# uno.net
KiCad netlist of a schematic drawn in EAGLE
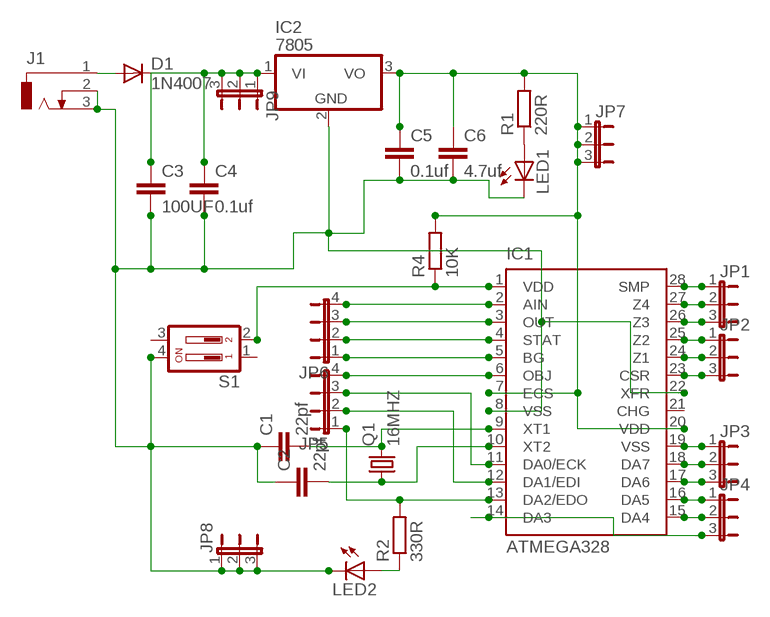
[diagram p0: schematic, sheet 1]

(export (version "E")
  (design (tool "Eeschema 10.0.6"))
  (components
    (comp (ref "C1")
      (value "22pf")
      (footprint "eagle-import:C2.5-2")
      (libsource (lib "eagle-import") (part "C2.5/2"))
    )
    (comp (ref "C2")
      (value "22pf")
      (footprint "eagle-import:C2.5-2")
      (libsource (lib "eagle-import") (part "C2.5/2"))
    )
    (comp (ref "C3")
      (value "100UF")
      (footprint "eagle-import:C2.5-2")
      (libsource (lib "eagle-import") (part "C2.5/2"))
    )
    (comp (ref "C4")
      (value "0.1uf")
      (footprint "eagle-import:C2.5-2")
      (libsource (lib "eagle-import") (part "C2.5/2"))
    )
    (comp (ref "C5")
      (value "0.1uf")
      (footprint "eagle-import:C2.5-2")
      (libsource (lib "eagle-import") (part "C2.5/2"))
    )
    (comp (ref "C6")
      (value "4.7uf")
      (footprint "eagle-import:C2.5-2")
      (libsource (lib "eagle-import") (part "C2.5/2"))
    )
    (comp (ref "D1")
      (value "1N4007")
      (footprint "eagle-import:DO41-10")
      (libsource (lib "eagle-import") (part "1N4004"))
    )
    (comp (ref "IC1")
      (value "ATMEGA328")
      (footprint "eagle-import:DIL28-3")
      (libsource (lib "eagle-import") (part "QT9701BD"))
    )
    (comp (ref "IC2")
      (value "7805")
      (footprint "eagle-import:TO220V")
      (libsource (lib "eagle-import") (part "78TV6"))
    )
    (comp (ref "J1")
      (value "DCJ0303")
      (footprint "eagle-import:DCJ0303")
      (libsource (lib "eagle-import") (part "DCJ0303"))
    )
    (comp (ref "JP1")
      (value "JP2E")
      (footprint "eagle-import:JP2")
      (libsource (lib "eagle-import") (part "JP2E"))
    )
    (comp (ref "JP2")
      (value "JP2E")
      (footprint "eagle-import:JP2")
      (libsource (lib "eagle-import") (part "JP2E"))
    )
    (comp (ref "JP3")
      (value "JP2E")
      (footprint "eagle-import:JP2")
      (libsource (lib "eagle-import") (part "JP2E"))
    )
    (comp (ref "JP4")
      (value "JP2E")
      (footprint "eagle-import:JP2")
      (libsource (lib "eagle-import") (part "JP2E"))
    )
    (comp (ref "JP5")
      (value "JP4E")
      (footprint "eagle-import:JP4")
      (libsource (lib "eagle-import") (part "JP4E"))
    )
    (comp (ref "JP6")
      (value "JP4E")
      (footprint "eagle-import:JP4")
      (libsource (lib "eagle-import") (part "JP4E"))
    )
    (comp (ref "JP7")
      (value "JP2E")
      (footprint "eagle-import:JP2")
      (libsource (lib "eagle-import") (part "JP2E"))
    )
    (comp (ref "JP8")
      (value "JP2E")
      (footprint "eagle-import:JP2")
      (libsource (lib "eagle-import") (part "JP2E"))
    )
    (comp (ref "JP9")
      (value "JP2E")
      (footprint "eagle-import:JP2")
      (libsource (lib "eagle-import") (part "JP2E"))
    )
    (comp (ref "LED1")
      (value "LED3MM")
      (footprint "eagle-import:LED3MM")
      (libsource (lib "eagle-import") (part "LED3MM"))
    )
    (comp (ref "LED2")
      (value "LED3MM")
      (footprint "eagle-import:LED3MM")
      (libsource (lib "eagle-import") (part "LED3MM"))
    )
    (comp (ref "Q1")
      (value "16MHZ")
      (footprint "eagle-import:HC49_S")
      (libsource (lib "eagle-import") (part "CRYSTALHC49S"))
    )
    (comp (ref "R1")
      (value "220R")
      (footprint "eagle-import:0207_10")
      (libsource (lib "eagle-import") (part "R-EU_0207/10"))
    )
    (comp (ref "R2")
      (value "330R")
      (footprint "eagle-import:0207_10")
      (libsource (lib "eagle-import") (part "R-EU_0207/10"))
    )
    (comp (ref "R4")
      (value "10K")
      (footprint "eagle-import:0207_10")
      (libsource (lib "eagle-import") (part "R-EU_0207/10"))
    )
    (comp (ref "S1")
      (value "DP02")
      (footprint "eagle-import:DP-02")
      (fields (field (name "MPN") "MCDP02"))
      (libsource (lib "eagle-import") (part "DP02"))
    )
  )
  (nets
    (net (code "1") (name "Net-(D1-PadA)") (class "Default")
      (node (ref "D1") (pin "A") (pinfunction "A_A") (pintype "passive"))
      (node (ref "J1") (pin "1") (pinfunction "1_1") (pintype "passive"))
    )
    (net (code "2") (name "Net-(IC1-AIN)") (class "Default")
      (node (ref "IC1") (pin "2") (pinfunction "AIN_2") (pintype "input"))
      (node (ref "JP6") (pin "4") (pinfunction "4_4") (pintype "passive"))
    )
    (net (code "3") (name "Net-(IC1-BG)") (class "Default")
      (node (ref "IC1") (pin "5") (pinfunction "BG_5") (pintype "input"))
      (node (ref "JP6") (pin "1") (pinfunction "1_1") (pintype "passive"))
    )
    (net (code "4") (name "Net-(IC1-CSR)") (class "Default")
      (node (ref "IC1") (pin "23") (pinfunction "CSR_23") (pintype "output"))
      (node (ref "JP2") (pin "3") (pinfunction "3_3") (pintype "passive"))
    )
    (net (code "5") (name "Net-(IC1-DA0{slash}ECK)") (class "Default")
      (node (ref "IC1") (pin "11") (pinfunction "DA0/ECK_11") (pintype "output"))
      (node (ref "JP5") (pin "3") (pinfunction "3_3") (pintype "passive"))
    )
    (net (code "6") (name "Net-(IC1-DA1{slash}EDI)") (class "Default")
      (node (ref "IC1") (pin "12") (pinfunction "DA1/EDI_12") (pintype "output"))
      (node (ref "JP5") (pin "2") (pinfunction "2_2") (pintype "passive"))
    )
    (net (code "7") (name "Net-(IC1-DA2{slash}EDO)") (class "Default")
      (node (ref "IC1") (pin "13") (pinfunction "DA2/EDO_13") (pintype "output"))
      (node (ref "JP5") (pin "1") (pinfunction "1_1") (pintype "passive"))
      (node (ref "R2") (pin "2") (pinfunction "2_2") (pintype "passive"))
    )
    (net (code "8") (name "Net-(IC1-DA3)") (class "Default")
      (node (ref "IC1") (pin "14") (pinfunction "DA3_14") (pintype "output"))
      (node (ref "JP4") (pin "3") (pinfunction "3_3") (pintype "passive"))
    )
    (net (code "9") (name "Net-(IC1-DA4)") (class "Default")
      (node (ref "IC1") (pin "15") (pinfunction "DA4_15") (pintype "output"))
      (node (ref "JP4") (pin "2") (pinfunction "2_2") (pintype "passive"))
    )
    (net (code "10") (name "Net-(IC1-DA5)") (class "Default")
      (node (ref "IC1") (pin "16") (pinfunction "DA5_16") (pintype "output"))
      (node (ref "JP4") (pin "1") (pinfunction "1_1") (pintype "passive"))
    )
    (net (code "11") (name "Net-(IC1-DA6)") (class "Default")
      (node (ref "IC1") (pin "17") (pinfunction "DA6_17") (pintype "output"))
      (node (ref "JP3") (pin "3") (pinfunction "3_3") (pintype "passive"))
    )
    (net (code "12") (name "Net-(IC1-DA7)") (class "Default")
      (node (ref "IC1") (pin "18") (pinfunction "DA7_18") (pintype "output"))
      (node (ref "JP3") (pin "2") (pinfunction "2_2") (pintype "passive"))
    )
    (net (code "13") (name "Net-(IC1-ECS)") (class "Default")
      (node (ref "C5") (pin "1") (pinfunction "1_1") (pintype "passive"))
      (node (ref "C6") (pin "1") (pinfunction "1_1") (pintype "passive"))
      (node (ref "IC1") (pin "20") (pinfunction "VDD_20") (pintype "input"))
      (node (ref "IC1") (pin "7") (pinfunction "ECS_7") (pintype "output"))
      (node (ref "IC2") (pin "3") (pinfunction "VO_3") (pintype "passive"))
      (node (ref "JP7") (pin "1") (pinfunction "1_1") (pintype "passive"))
      (node (ref "JP7") (pin "2") (pinfunction "2_2") (pintype "passive"))
      (node (ref "JP7") (pin "3") (pinfunction "3_3") (pintype "passive"))
      (node (ref "R1") (pin "2") (pinfunction "2_2") (pintype "passive"))
      (node (ref "R4") (pin "2") (pinfunction "2_2") (pintype "passive"))
    )
    (net (code "14") (name "Net-(IC1-OBJ)") (class "Default")
      (node (ref "IC1") (pin "6") (pinfunction "OBJ_6") (pintype "input"))
      (node (ref "JP5") (pin "4") (pinfunction "4_4") (pintype "passive"))
    )
    (net (code "15") (name "Net-(IC1-OUT)") (class "Default")
      (node (ref "IC1") (pin "3") (pinfunction "OUT_3") (pintype "output"))
      (node (ref "JP6") (pin "3") (pinfunction "3_3") (pintype "passive"))
    )
    (net (code "16") (name "Net-(IC1-SMP)") (class "Default")
      (node (ref "IC1") (pin "28") (pinfunction "SMP_28") (pintype "output"))
      (node (ref "JP1") (pin "1") (pinfunction "1_1") (pintype "passive"))
    )
    (net (code "17") (name "Net-(IC1-STAT)") (class "Default")
      (node (ref "IC1") (pin "4") (pinfunction "STAT_4") (pintype "output"))
      (node (ref "JP6") (pin "2") (pinfunction "2_2") (pintype "passive"))
    )
    (net (code "18") (name "Net-(IC1-VDD-Pad1)") (class "Default")
      (node (ref "IC1") (pin "1") (pinfunction "VDD_1") (pintype "input"))
      (node (ref "R4") (pin "1") (pinfunction "1_1") (pintype "passive"))
      (node (ref "S1") (pin "2") (pinfunction "2_2") (pintype "passive"))
    )
    (net (code "19") (name "Net-(IC1-VSS-Pad19)") (class "Default")
      (node (ref "IC1") (pin "19") (pinfunction "VSS_19") (pintype "input"))
      (node (ref "JP3") (pin "1") (pinfunction "1_1") (pintype "passive"))
    )
    (net (code "20") (name "Net-(IC1-XFR)") (class "Default")
      (node (ref "C1") (pin "1") (pinfunction "1_1") (pintype "passive"))
      (node (ref "C2") (pin "1") (pinfunction "1_1") (pintype "passive"))
      (node (ref "C3") (pin "2") (pinfunction "2_2") (pintype "passive"))
      (node (ref "C4") (pin "2") (pinfunction "2_2") (pintype "passive"))
      (node (ref "C5") (pin "2") (pinfunction "2_2") (pintype "passive"))
      (node (ref "C6") (pin "2") (pinfunction "2_2") (pintype "passive"))
      (node (ref "IC1") (pin "22") (pinfunction "XFR_22") (pintype "output"))
      (node (ref "IC1") (pin "8") (pinfunction "VSS_8") (pintype "input"))
      (node (ref "IC2") (pin "2") (pinfunction "GND_2") (pintype "passive"))
      (node (ref "J1") (pin "2") (pinfunction "2_2") (pintype "passive"))
      (node (ref "J1") (pin "3") (pinfunction "3_3") (pintype "passive"))
      (node (ref "JP8") (pin "1") (pinfunction "1_1") (pintype "passive"))
      (node (ref "JP8") (pin "2") (pinfunction "2_2") (pintype "passive"))
      (node (ref "JP8") (pin "3") (pinfunction "3_3") (pintype "passive"))
      (node (ref "LED1") (pin "K") (pinfunction "C_K") (pintype "passive"))
      (node (ref "LED2") (pin "K") (pinfunction "C_K") (pintype "passive"))
      (node (ref "S1") (pin "4") (pinfunction "4_4") (pintype "passive"))
    )
    (net (code "21") (name "Net-(IC1-XT1)") (class "Default")
      (node (ref "C1") (pin "2") (pinfunction "2_2") (pintype "passive"))
      (node (ref "IC1") (pin "9") (pinfunction "XT1_9") (pintype "input"))
      (node (ref "Q1") (pin "2") (pinfunction "2_2") (pintype "passive"))
    )
    (net (code "22") (name "Net-(IC1-XT2)") (class "Default")
      (node (ref "C2") (pin "2") (pinfunction "2_2") (pintype "passive"))
      (node (ref "IC1") (pin "10") (pinfunction "XT2_10") (pintype "output"))
      (node (ref "Q1") (pin "1") (pinfunction "1_1") (pintype "passive"))
    )
    (net (code "23") (name "Net-(IC1-Z1)") (class "Default")
      (node (ref "IC1") (pin "24") (pinfunction "Z1_24") (pintype "output"))
      (node (ref "JP2") (pin "2") (pinfunction "2_2") (pintype "passive"))
    )
    (net (code "24") (name "Net-(IC1-Z2)") (class "Default")
      (node (ref "IC1") (pin "25") (pinfunction "Z2_25") (pintype "output"))
      (node (ref "JP2") (pin "1") (pinfunction "1_1") (pintype "passive"))
    )
    (net (code "25") (name "Net-(IC1-Z3)") (class "Default")
      (node (ref "IC1") (pin "26") (pinfunction "Z3_26") (pintype "output"))
      (node (ref "JP1") (pin "3") (pinfunction "3_3") (pintype "passive"))
    )
    (net (code "26") (name "Net-(IC1-Z4)") (class "Default")
      (node (ref "IC1") (pin "27") (pinfunction "Z4_27") (pintype "output"))
      (node (ref "JP1") (pin "2") (pinfunction "2_2") (pintype "passive"))
    )
    (net (code "27") (name "Net-(IC2-VI)") (class "Default")
      (node (ref "C3") (pin "1") (pinfunction "1_1") (pintype "passive"))
      (node (ref "C4") (pin "1") (pinfunction "1_1") (pintype "passive"))
      (node (ref "D1") (pin "C") (pinfunction "C_C") (pintype "passive"))
      (node (ref "IC2") (pin "1") (pinfunction "VI_1") (pintype "input"))
      (node (ref "JP9") (pin "1") (pinfunction "1_1") (pintype "passive"))
      (node (ref "JP9") (pin "2") (pinfunction "2_2") (pintype "passive"))
      (node (ref "JP9") (pin "3") (pinfunction "3_3") (pintype "passive"))
    )
    (net (code "28") (name "Net-(LED1-PadA)") (class "Default")
      (node (ref "LED1") (pin "A") (pinfunction "A_A") (pintype "passive"))
      (node (ref "R1") (pin "1") (pinfunction "1_1") (pintype "passive"))
    )
    (net (code "29") (name "Net-(LED2-PadA)") (class "Default")
      (node (ref "LED2") (pin "A") (pinfunction "A_A") (pintype "passive"))
      (node (ref "R2") (pin "1") (pinfunction "1_1") (pintype "passive"))
    )
    (net (code "30") (name "unconnected-(IC1-CHG-Pad21)") (class "Default")
      (node (ref "IC1") (pin "21") (pinfunction "CHG_21") (pintype "output"))
    )
    (net (code "31") (name "unconnected-(S1-Pad1)") (class "Default")
      (node (ref "S1") (pin "1") (pinfunction "1_1") (pintype "passive"))
    )
    (net (code "32") (name "unconnected-(S1-Pad3)") (class "Default")
      (node (ref "S1") (pin "3") (pinfunction "3_3") (pintype "passive"))
    )
  )
)
